# 05_06_mux_gate.net
KiCad netlist of a schematic drawn in Altium Designer
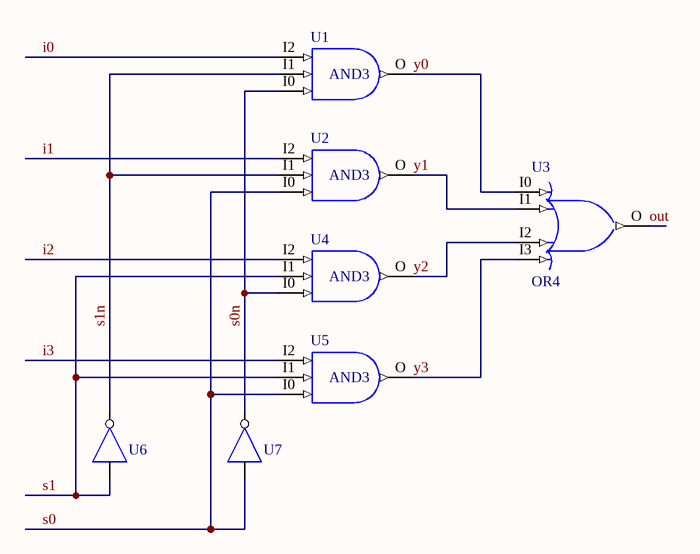
[diagram p0: 05_06_mux_gate.SchDoc]

(export (version "E")
  (design (tool "Eeschema 10.0.6"))
  (components
    (comp (ref "U1")
      (value "AND3")
      (description "3-Input AND Gate")
      (fields (field (name "PUBLISHER") "Altium Limited"))
      (libsource (lib "CUPL PLD Programming") (part "AND3"))
    )
    (comp (ref "U2")
      (value "AND3")
      (description "3-Input AND Gate")
      (fields (field (name "PUBLISHER") "Altium Limited"))
      (libsource (lib "CUPL PLD Programming") (part "AND3"))
    )
    (comp (ref "U3")
      (value "OR4")
      (description "4-Input OR Gate")
      (fields (field (name "PUBLISHER") "Altium Limited"))
      (libsource (lib "CUPL PLD Programming") (part "OR4"))
    )
    (comp (ref "U4")
      (value "AND3")
      (description "3-Input AND Gate")
      (fields (field (name "PUBLISHER") "Altium Limited"))
      (libsource (lib "CUPL PLD Programming") (part "AND3"))
    )
    (comp (ref "U5")
      (value "AND3")
      (description "3-Input AND Gate")
      (fields (field (name "PUBLISHER") "Altium Limited"))
      (libsource (lib "CUPL PLD Programming") (part "AND3"))
    )
    (comp (ref "U6")
      (value "not")
      (description "1-bit General Purpose (Non-inverting) Buffer")
      (libsource (lib "BlockSchematics (DESKTOP-V82PM3U conflicted copy 2020-01-27 14 16 44)") (part "BUF"))
    )
    (comp (ref "U7")
      (value "not")
      (description "1-bit General Purpose (Non-inverting) Buffer")
      (libsource (lib "BlockSchematics (DESKTOP-V82PM3U conflicted copy 2020-01-27 14 16 44)") (part "BUF"))
    )
  )
  (nets
    (net (code "1") (name "/i0") (class "Default")
      (node (ref "U1") (pin "I2") (pinfunction "I2_I2") (pintype "input"))
    )
    (net (code "2") (name "/i1") (class "Default")
      (node (ref "U2") (pin "I2") (pinfunction "I2_I2") (pintype "input"))
    )
    (net (code "3") (name "/i2") (class "Default")
      (node (ref "U4") (pin "I2") (pinfunction "I2_I2") (pintype "input"))
    )
    (net (code "4") (name "/i3") (class "Default")
      (node (ref "U5") (pin "I2") (pinfunction "I2_I2") (pintype "input"))
    )
    (net (code "5") (name "/out") (class "Default")
      (node (ref "U3") (pin "O") (pinfunction "O_O") (pintype "output"))
    )
    (net (code "6") (name "/s0") (class "Default")
      (node (ref "U2") (pin "I0") (pinfunction "I0_I0") (pintype "input"))
      (node (ref "U5") (pin "I0") (pinfunction "I0_I0") (pintype "input"))
      (node (ref "U7") (pin "i") (pinfunction "i_i") (pintype "passive"))
    )
    (net (code "7") (name "/s0n") (class "Default")
      (node (ref "U1") (pin "I0") (pinfunction "I0_I0") (pintype "input"))
      (node (ref "U4") (pin "I0") (pinfunction "I0_I0") (pintype "input"))
      (node (ref "U7") (pin "o") (pinfunction "o_o") (pintype "passive"))
    )
    (net (code "8") (name "/s1") (class "Default")
      (node (ref "U4") (pin "I1") (pinfunction "I1_I1") (pintype "input"))
      (node (ref "U5") (pin "I1") (pinfunction "I1_I1") (pintype "input"))
      (node (ref "U6") (pin "i") (pinfunction "i_i") (pintype "passive"))
    )
    (net (code "9") (name "/s1n") (class "Default")
      (node (ref "U1") (pin "I1") (pinfunction "I1_I1") (pintype "input"))
      (node (ref "U2") (pin "I1") (pinfunction "I1_I1") (pintype "input"))
      (node (ref "U6") (pin "o") (pinfunction "o_o") (pintype "passive"))
    )
    (net (code "10") (name "/y0") (class "Default")
      (node (ref "U1") (pin "O") (pinfunction "O_O") (pintype "output"))
      (node (ref "U3") (pin "I0") (pinfunction "I0_I0") (pintype "input"))
    )
    (net (code "11") (name "/y1") (class "Default")
      (node (ref "U2") (pin "O") (pinfunction "O_O") (pintype "output"))
      (node (ref "U3") (pin "I1") (pinfunction "I1_I1") (pintype "input"))
    )
    (net (code "12") (name "/y2") (class "Default")
      (node (ref "U3") (pin "I2") (pinfunction "I2_I2") (pintype "input"))
      (node (ref "U4") (pin "O") (pinfunction "O_O") (pintype "output"))
    )
    (net (code "13") (name "/y3") (class "Default")
      (node (ref "U3") (pin "I3") (pinfunction "I3_I3") (pintype "input"))
      (node (ref "U5") (pin "O") (pinfunction "O_O") (pintype "output"))
    )
  )
)
